# PowerDistributionBoard.net
KiCad netlist of a schematic drawn in EAGLE
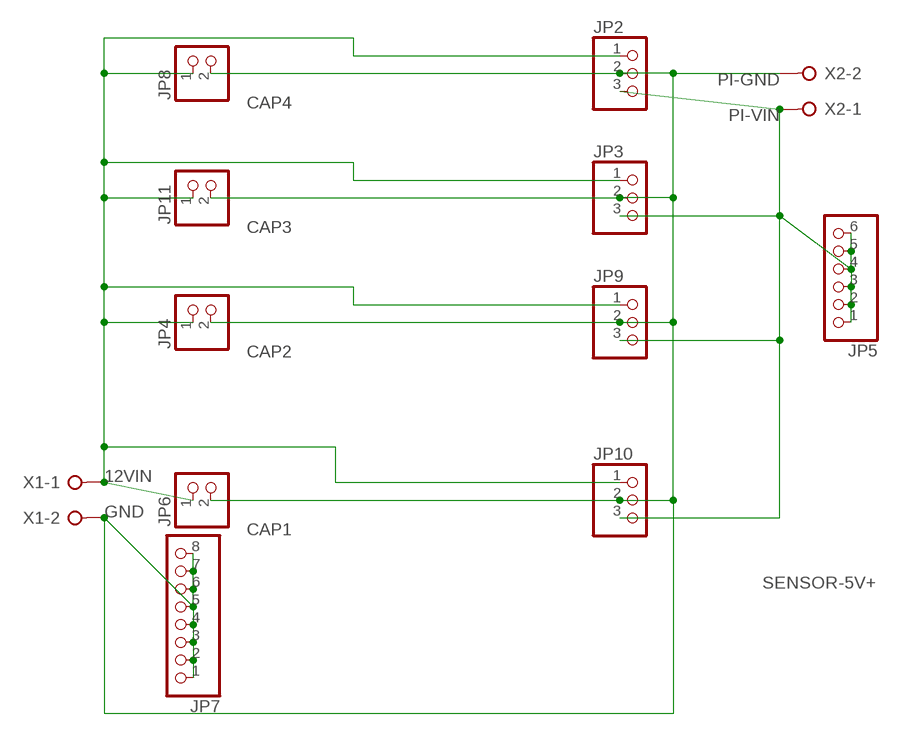
[diagram p0: schematic, sheet 1]

(export (version "E")
  (design (tool "Eeschema 10.0.6"))
  (components
    (comp (ref "JP2")
      (value "PINHD-1X3")
      (footprint "eagle-import:1X03")
      (libsource (lib "eagle-import") (part "PINHD-1X3"))
    )
    (comp (ref "JP3")
      (value "PINHD-1X3")
      (footprint "eagle-import:1X03")
      (libsource (lib "eagle-import") (part "PINHD-1X3"))
    )
    (comp (ref "JP4")
      (value "PINHD-1X2")
      (footprint "eagle-import:1X02")
      (libsource (lib "eagle-import") (part "PINHD-1X2"))
    )
    (comp (ref "JP5")
      (value "PINHD-1X6")
      (footprint "eagle-import:1X06")
      (libsource (lib "eagle-import") (part "PINHD-1X6"))
    )
    (comp (ref "JP6")
      (value "PINHD-1X2")
      (footprint "eagle-import:1X02")
      (libsource (lib "eagle-import") (part "PINHD-1X2"))
    )
    (comp (ref "JP7")
      (value "PINHD-1X8")
      (footprint "eagle-import:1X08")
      (libsource (lib "eagle-import") (part "PINHD-1X8"))
    )
    (comp (ref "JP8")
      (value "PINHD-1X2")
      (footprint "eagle-import:1X02")
      (libsource (lib "eagle-import") (part "PINHD-1X2"))
    )
    (comp (ref "JP9")
      (value "PINHD-1X3")
      (footprint "eagle-import:1X03")
      (libsource (lib "eagle-import") (part "PINHD-1X3"))
    )
    (comp (ref "JP10")
      (value "PINHD-1X3")
      (footprint "eagle-import:1X03")
      (libsource (lib "eagle-import") (part "PINHD-1X3"))
    )
    (comp (ref "JP11")
      (value "PINHD-1X2")
      (footprint "eagle-import:1X02")
      (libsource (lib "eagle-import") (part "PINHD-1X2"))
    )
    (comp (ref "X1")
      (value "W237-02P")
      (footprint "eagle-import:W237-132")
      (libsource (lib "eagle-import") (part "W237-02P"))
    )
    (comp (ref "X2")
      (value "W237-02P")
      (footprint "eagle-import:W237-132")
      (libsource (lib "eagle-import") (part "W237-02P"))
    )
  )
  (nets
    (net (code "1") (name "/SENSOR-5V+") (class "Default")
      (node (ref "JP10") (pin "3") (pinfunction "3_3") (pintype "passive"))
      (node (ref "JP2") (pin "3") (pinfunction "3_3") (pintype "passive"))
      (node (ref "JP3") (pin "3") (pinfunction "3_3") (pintype "passive"))
      (node (ref "JP5") (pin "1") (pinfunction "1_1") (pintype "passive"))
      (node (ref "JP5") (pin "2") (pinfunction "2_2") (pintype "passive"))
      (node (ref "JP5") (pin "3") (pinfunction "3_3") (pintype "passive"))
      (node (ref "JP5") (pin "4") (pinfunction "4_4") (pintype "passive"))
      (node (ref "JP5") (pin "5") (pinfunction "5_5") (pintype "passive"))
      (node (ref "JP5") (pin "6") (pinfunction "6_6") (pintype "passive"))
      (node (ref "JP9") (pin "3") (pinfunction "3_3") (pintype "passive"))
      (node (ref "X2") (pin "1") (pinfunction "KL_1") (pintype "passive"))
    )
    (net (code "2") (name "Net-(X1A-KL)") (class "Default")
      (node (ref "JP10") (pin "1") (pinfunction "1_1") (pintype "passive"))
      (node (ref "JP11") (pin "1") (pinfunction "1_1") (pintype "passive"))
      (node (ref "JP2") (pin "1") (pinfunction "1_1") (pintype "passive"))
      (node (ref "JP3") (pin "1") (pinfunction "1_1") (pintype "passive"))
      (node (ref "JP4") (pin "1") (pinfunction "1_1") (pintype "passive"))
      (node (ref "JP6") (pin "1") (pinfunction "1_1") (pintype "passive"))
      (node (ref "JP8") (pin "1") (pinfunction "1_1") (pintype "passive"))
      (node (ref "JP9") (pin "1") (pinfunction "1_1") (pintype "passive"))
      (node (ref "X1") (pin "1") (pinfunction "KL_1") (pintype "passive"))
    )
    (net (code "3") (name "Net-(X1B-KL)") (class "Default")
      (node (ref "JP10") (pin "2") (pinfunction "2_2") (pintype "passive"))
      (node (ref "JP11") (pin "2") (pinfunction "2_2") (pintype "passive"))
      (node (ref "JP2") (pin "2") (pinfunction "2_2") (pintype "passive"))
      (node (ref "JP3") (pin "2") (pinfunction "2_2") (pintype "passive"))
      (node (ref "JP4") (pin "2") (pinfunction "2_2") (pintype "passive"))
      (node (ref "JP6") (pin "2") (pinfunction "2_2") (pintype "passive"))
      (node (ref "JP7") (pin "1") (pinfunction "1_1") (pintype "passive"))
      (node (ref "JP7") (pin "2") (pinfunction "2_2") (pintype "passive"))
      (node (ref "JP7") (pin "3") (pinfunction "3_3") (pintype "passive"))
      (node (ref "JP7") (pin "4") (pinfunction "4_4") (pintype "passive"))
      (node (ref "JP7") (pin "5") (pinfunction "5_5") (pintype "passive"))
      (node (ref "JP7") (pin "6") (pinfunction "6_6") (pintype "passive"))
      (node (ref "JP7") (pin "7") (pinfunction "7_7") (pintype "passive"))
      (node (ref "JP7") (pin "8") (pinfunction "8_8") (pintype "passive"))
      (node (ref "JP8") (pin "2") (pinfunction "2_2") (pintype "passive"))
      (node (ref "JP9") (pin "2") (pinfunction "2_2") (pintype "passive"))
      (node (ref "X1") (pin "2") (pinfunction "KL_2") (pintype "passive"))
      (node (ref "X2") (pin "2") (pinfunction "KL_2") (pintype "passive"))
    )
  )
)
